# audio_breakout.net
KiCad netlist of a schematic drawn in EAGLE
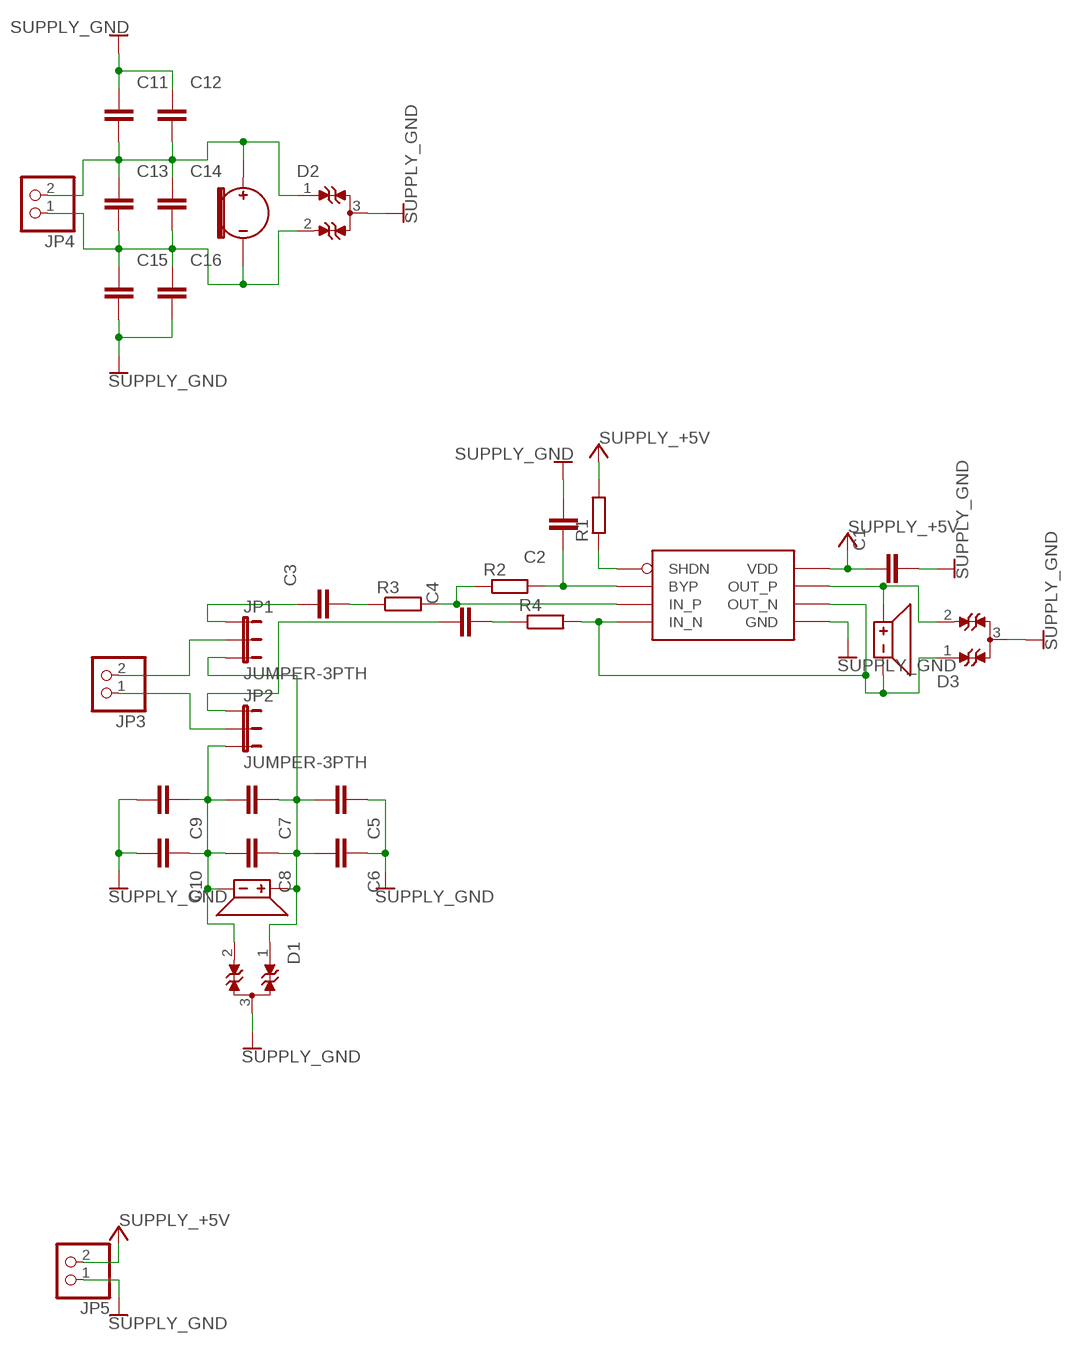
[diagram p0: schematic, sheet 1]

(export (version "E")
  (design (tool "Eeschema 10.0.6"))
  (components
    (comp (ref "C1")
      (value "CAPACITOR_NPOL-0603")
      (footprint "eagle-import:C603")
      (libsource (lib "eagle-import") (part "CAPACITOR_NPOL-0603"))
    )
    (comp (ref "C2")
      (value "CAPACITOR_NPOL-0603")
      (footprint "eagle-import:C603")
      (libsource (lib "eagle-import") (part "CAPACITOR_NPOL-0603"))
    )
    (comp (ref "C3")
      (value "CAPACITOR_NPOL-0603")
      (footprint "eagle-import:C603")
      (libsource (lib "eagle-import") (part "CAPACITOR_NPOL-0603"))
    )
    (comp (ref "C4")
      (value "CAPACITOR_NPOL-0603")
      (footprint "eagle-import:C603")
      (libsource (lib "eagle-import") (part "CAPACITOR_NPOL-0603"))
    )
    (comp (ref "C5")
      (value "CAPACITOR_NPOL-0603")
      (footprint "eagle-import:C603")
      (libsource (lib "eagle-import") (part "CAPACITOR_NPOL-0603"))
    )
    (comp (ref "C6")
      (value "CAPACITOR_NPOL-0603")
      (footprint "eagle-import:C603")
      (libsource (lib "eagle-import") (part "CAPACITOR_NPOL-0603"))
    )
    (comp (ref "C7")
      (value "CAPACITOR_NPOL-0603")
      (footprint "eagle-import:C603")
      (libsource (lib "eagle-import") (part "CAPACITOR_NPOL-0603"))
    )
    (comp (ref "C8")
      (value "CAPACITOR_NPOL-0603")
      (footprint "eagle-import:C603")
      (libsource (lib "eagle-import") (part "CAPACITOR_NPOL-0603"))
    )
    (comp (ref "C9")
      (value "CAPACITOR_NPOL-0603")
      (footprint "eagle-import:C603")
      (libsource (lib "eagle-import") (part "CAPACITOR_NPOL-0603"))
    )
    (comp (ref "C10")
      (value "CAPACITOR_NPOL-0603")
      (footprint "eagle-import:C603")
      (libsource (lib "eagle-import") (part "CAPACITOR_NPOL-0603"))
    )
    (comp (ref "C11")
      (value "CAPACITOR_NPOL-0603")
      (footprint "eagle-import:C603")
      (libsource (lib "eagle-import") (part "CAPACITOR_NPOL-0603"))
    )
    (comp (ref "C12")
      (value "CAPACITOR_NPOL-0603")
      (footprint "eagle-import:C603")
      (libsource (lib "eagle-import") (part "CAPACITOR_NPOL-0603"))
    )
    (comp (ref "C13")
      (value "CAPACITOR_NPOL-0603")
      (footprint "eagle-import:C603")
      (libsource (lib "eagle-import") (part "CAPACITOR_NPOL-0603"))
    )
    (comp (ref "C14")
      (value "CAPACITOR_NPOL-0603")
      (footprint "eagle-import:C603")
      (libsource (lib "eagle-import") (part "CAPACITOR_NPOL-0603"))
    )
    (comp (ref "C15")
      (value "CAPACITOR_NPOL-0603")
      (footprint "eagle-import:C603")
      (libsource (lib "eagle-import") (part "CAPACITOR_NPOL-0603"))
    )
    (comp (ref "C16")
      (value "CAPACITOR_NPOL-0603")
      (footprint "eagle-import:C603")
      (libsource (lib "eagle-import") (part "CAPACITOR_NPOL-0603"))
    )
    (comp (ref "D1")
      (value "WE-TVS_824022")
      (footprint "eagle-import:WE-TVS_SOT23-3L")
      (fields (field (name "MPN") "824022"))
      (libsource (lib "eagle-import") (part "WE-TVS_824022"))
    )
    (comp (ref "D2")
      (value "WE-TVS_824022")
      (footprint "eagle-import:WE-TVS_SOT23-3L")
      (fields (field (name "MPN") "824022"))
      (libsource (lib "eagle-import") (part "WE-TVS_824022"))
    )
    (comp (ref "D3")
      (value "WE-TVS_824022")
      (footprint "eagle-import:WE-TVS_SOT23-3L")
      (fields (field (name "MPN") "824022"))
      (libsource (lib "eagle-import") (part "WE-TVS_824022"))
    )
    (comp (ref "JP1")
      (value "JUMPER-3PTH")
      (footprint "eagle-import:1X03")
      (libsource (lib "eagle-import") (part "JUMPER-3PTH"))
    )
    (comp (ref "JP2")
      (value "JUMPER-3PTH")
      (footprint "eagle-import:1X03")
      (libsource (lib "eagle-import") (part "JUMPER-3PTH"))
    )
    (comp (ref "JP3")
      (value "PINHD-1X2")
      (footprint "eagle-import:1X02")
      (libsource (lib "eagle-import") (part "PINHD-1X2"))
    )
    (comp (ref "JP4")
      (value "PINHD-1X2")
      (footprint "eagle-import:1X02")
      (libsource (lib "eagle-import") (part "PINHD-1X2"))
    )
    (comp (ref "JP5")
      (value "PINHD-1X2")
      (footprint "eagle-import:1X02")
      (libsource (lib "eagle-import") (part "PINHD-1X2"))
    )
    (comp (ref "R1")
      (value "RESISTOR-0603")
      (footprint "eagle-import:R603")
      (libsource (lib "eagle-import") (part "RESISTOR-0603"))
    )
    (comp (ref "R2")
      (value "RESISTOR-0603")
      (footprint "eagle-import:R603")
      (libsource (lib "eagle-import") (part "RESISTOR-0603"))
    )
    (comp (ref "R3")
      (value "RESISTOR-0603")
      (footprint "eagle-import:R603")
      (libsource (lib "eagle-import") (part "RESISTOR-0603"))
    )
    (comp (ref "R4")
      (value "RESISTOR-0603")
      (footprint "eagle-import:R603")
      (libsource (lib "eagle-import") (part "RESISTOR-0603"))
    )
    (comp (ref "U$1")
      (value "LM4890")
      (footprint "eagle-import:SOIC-8-NARROW")
      (libsource (lib "eagle-import") (part "LM4890"))
    )
    (comp (ref "U$2")
      (value "SPEAKER-2403-260-00001")
      (footprint "eagle-import:2403-260-00001")
      (libsource (lib "eagle-import") (part "SPEAKER-2403-260-00001"))
    )
    (comp (ref "U$3")
      (value "SPEAKER-2403-260-00031")
      (footprint "eagle-import:2403-260-00031")
      (libsource (lib "eagle-import") (part "SPEAKER-2403-260-00031"))
    )
    (comp (ref "U$4")
      (value "MIC-ELECTRET-9.7MM")
      (footprint "eagle-import:9.7MM-ELECTRET")
      (libsource (lib "eagle-import") (part "MIC-ELECTRET-9.7MM"))
    )
  )
  (nets
    (net (code "1") (name "Net-(C3-Pad1)") (class "Default")
      (node (ref "C3") (pin "1") (pinfunction "1_1") (pintype "passive"))
      (node (ref "JP1") (pin "1") (pinfunction "1_1") (pintype "passive"))
    )
    (net (code "2") (name "Net-(C3-Pad2)") (class "Default")
      (node (ref "C3") (pin "2") (pinfunction "2_2") (pintype "passive"))
      (node (ref "R3") (pin "1") (pinfunction "1_1") (pintype "passive"))
    )
    (net (code "3") (name "Net-(C4-Pad1)") (class "Default")
      (node (ref "C4") (pin "1") (pinfunction "1_1") (pintype "passive"))
      (node (ref "JP2") (pin "1") (pinfunction "1_1") (pintype "passive"))
    )
    (net (code "4") (name "Net-(C4-Pad2)") (class "Default")
      (node (ref "C4") (pin "2") (pinfunction "2_2") (pintype "passive"))
      (node (ref "R4") (pin "1") (pinfunction "1_1") (pintype "passive"))
    )
    (net (code "5") (name "Net-(C5-Pad2)") (class "Default")
      (node (ref "C5") (pin "2") (pinfunction "2_2") (pintype "passive"))
      (node (ref "C6") (pin "2") (pinfunction "2_2") (pintype "passive"))
      (node (ref "C7") (pin "1") (pinfunction "1_1") (pintype "passive"))
      (node (ref "C8") (pin "1") (pinfunction "1_1") (pintype "passive"))
      (node (ref "D1") (pin "1") (pinfunction "1_1") (pintype "passive"))
      (node (ref "JP1") (pin "3") (pinfunction "3_3") (pintype "passive"))
      (node (ref "U$3") (pin "+") (pinfunction "+_+") (pintype "power_in"))
    )
    (net (code "6") (name "Net-(C10-Pad1)") (class "Default")
      (node (ref "C10") (pin "1") (pinfunction "1_1") (pintype "passive"))
      (node (ref "C7") (pin "2") (pinfunction "2_2") (pintype "passive"))
      (node (ref "C8") (pin "2") (pinfunction "2_2") (pintype "passive"))
      (node (ref "C9") (pin "1") (pinfunction "1_1") (pintype "passive"))
      (node (ref "D1") (pin "2") (pinfunction "2_2") (pintype "passive"))
      (node (ref "JP2") (pin "3") (pinfunction "3_3") (pintype "passive"))
      (node (ref "U$3") (pin "-") (pinfunction "-_-") (pintype "power_in"))
    )
    (net (code "7") (name "Net-(C11-Pad2)") (class "Default")
      (node (ref "C11") (pin "2") (pinfunction "2_2") (pintype "passive"))
      (node (ref "C12") (pin "2") (pinfunction "2_2") (pintype "passive"))
      (node (ref "C13") (pin "1") (pinfunction "1_1") (pintype "passive"))
      (node (ref "C14") (pin "1") (pinfunction "1_1") (pintype "passive"))
      (node (ref "D2") (pin "1") (pinfunction "1_1") (pintype "passive"))
      (node (ref "JP4") (pin "2") (pinfunction "2_2") (pintype "passive"))
      (node (ref "U$4") (pin "+") (pinfunction "+_+") (pintype "bidirectional"))
    )
    (net (code "8") (name "Net-(C13-Pad2)") (class "Default")
      (node (ref "C13") (pin "2") (pinfunction "2_2") (pintype "passive"))
      (node (ref "C14") (pin "2") (pinfunction "2_2") (pintype "passive"))
      (node (ref "C15") (pin "1") (pinfunction "1_1") (pintype "passive"))
      (node (ref "C16") (pin "1") (pinfunction "1_1") (pintype "passive"))
      (node (ref "D2") (pin "2") (pinfunction "2_2") (pintype "passive"))
      (node (ref "JP4") (pin "1") (pinfunction "1_1") (pintype "passive"))
      (node (ref "U$4") (pin "-") (pinfunction "-_-") (pintype "bidirectional"))
    )
    (net (code "9") (name "Net-(JP1-Pad2)") (class "Default")
      (node (ref "JP1") (pin "2") (pinfunction "2_2") (pintype "passive"))
      (node (ref "JP3") (pin "2") (pinfunction "2_2") (pintype "passive"))
    )
    (net (code "10") (name "Net-(JP2-Pad2)") (class "Default")
      (node (ref "JP2") (pin "2") (pinfunction "2_2") (pintype "passive"))
      (node (ref "JP3") (pin "1") (pinfunction "1_1") (pintype "passive"))
    )
    (net (code "11") (name "Net-(U$1-BYP)") (class "Default")
      (node (ref "C2") (pin "1") (pinfunction "1_1") (pintype "passive"))
      (node (ref "R2") (pin "2") (pinfunction "2_2") (pintype "passive"))
      (node (ref "U$1") (pin "2") (pinfunction "BYP_2") (pintype "input"))
    )
    (net (code "12") (name "Net-(U$1-IN_N)") (class "Default")
      (node (ref "D3") (pin "1") (pinfunction "1_1") (pintype "passive"))
      (node (ref "R4") (pin "2") (pinfunction "2_2") (pintype "passive"))
      (node (ref "U$1") (pin "4") (pinfunction "IN_N_4") (pintype "input"))
      (node (ref "U$1") (pin "5") (pinfunction "OUT_N_5") (pintype "output"))
      (node (ref "U$2") (pin "-") (pinfunction "-_-") (pintype "power_in"))
    )
    (net (code "13") (name "Net-(U$1-IN_P)") (class "Default")
      (node (ref "R2") (pin "1") (pinfunction "1_1") (pintype "passive"))
      (node (ref "R3") (pin "2") (pinfunction "2_2") (pintype "passive"))
      (node (ref "U$1") (pin "3") (pinfunction "IN_P_3") (pintype "input"))
    )
    (net (code "14") (name "Net-(U$1-OUT_P)") (class "Default")
      (node (ref "D3") (pin "2") (pinfunction "2_2") (pintype "passive"))
      (node (ref "U$1") (pin "8") (pinfunction "OUT_P_8") (pintype "output"))
      (node (ref "U$2") (pin "+") (pinfunction "+_+") (pintype "power_in"))
    )
    (net (code "15") (name "Net-(U$1-SHDN)") (class "Default")
      (node (ref "R1") (pin "1") (pinfunction "1_1") (pintype "passive"))
      (node (ref "U$1") (pin "1") (pinfunction "SHDN_1") (pintype "input"))
    )
    (net (code "16") (name "SUPPLY_+5V") (class "Default")
      (node (ref "C1") (pin "1") (pinfunction "1_1") (pintype "passive"))
      (node (ref "JP5") (pin "2") (pinfunction "2_2") (pintype "passive"))
      (node (ref "R1") (pin "2") (pinfunction "2_2") (pintype "passive"))
      (node (ref "U$1") (pin "6") (pinfunction "VDD_6") (pintype "power_in"))
    )
    (net (code "17") (name "SUPPLY_GND") (class "Default")
      (node (ref "C1") (pin "2") (pinfunction "2_2") (pintype "passive"))
      (node (ref "C10") (pin "2") (pinfunction "2_2") (pintype "passive"))
      (node (ref "C11") (pin "1") (pinfunction "1_1") (pintype "passive"))
      (node (ref "C12") (pin "1") (pinfunction "1_1") (pintype "passive"))
      (node (ref "C15") (pin "2") (pinfunction "2_2") (pintype "passive"))
      (node (ref "C16") (pin "2") (pinfunction "2_2") (pintype "passive"))
      (node (ref "C2") (pin "2") (pinfunction "2_2") (pintype "passive"))
      (node (ref "C5") (pin "1") (pinfunction "1_1") (pintype "passive"))
      (node (ref "C6") (pin "1") (pinfunction "1_1") (pintype "passive"))
      (node (ref "C9") (pin "2") (pinfunction "2_2") (pintype "passive"))
      (node (ref "D1") (pin "3") (pinfunction "GND_3") (pintype "power_in"))
      (node (ref "D2") (pin "3") (pinfunction "GND_3") (pintype "power_in"))
      (node (ref "D3") (pin "3") (pinfunction "GND_3") (pintype "power_in"))
      (node (ref "JP5") (pin "1") (pinfunction "1_1") (pintype "passive"))
      (node (ref "U$1") (pin "7") (pinfunction "GND_7") (pintype "power_in"))
    )
  )
)
